# fmc_connector.net
KiCad netlist of a schematic drawn in Altium Designer
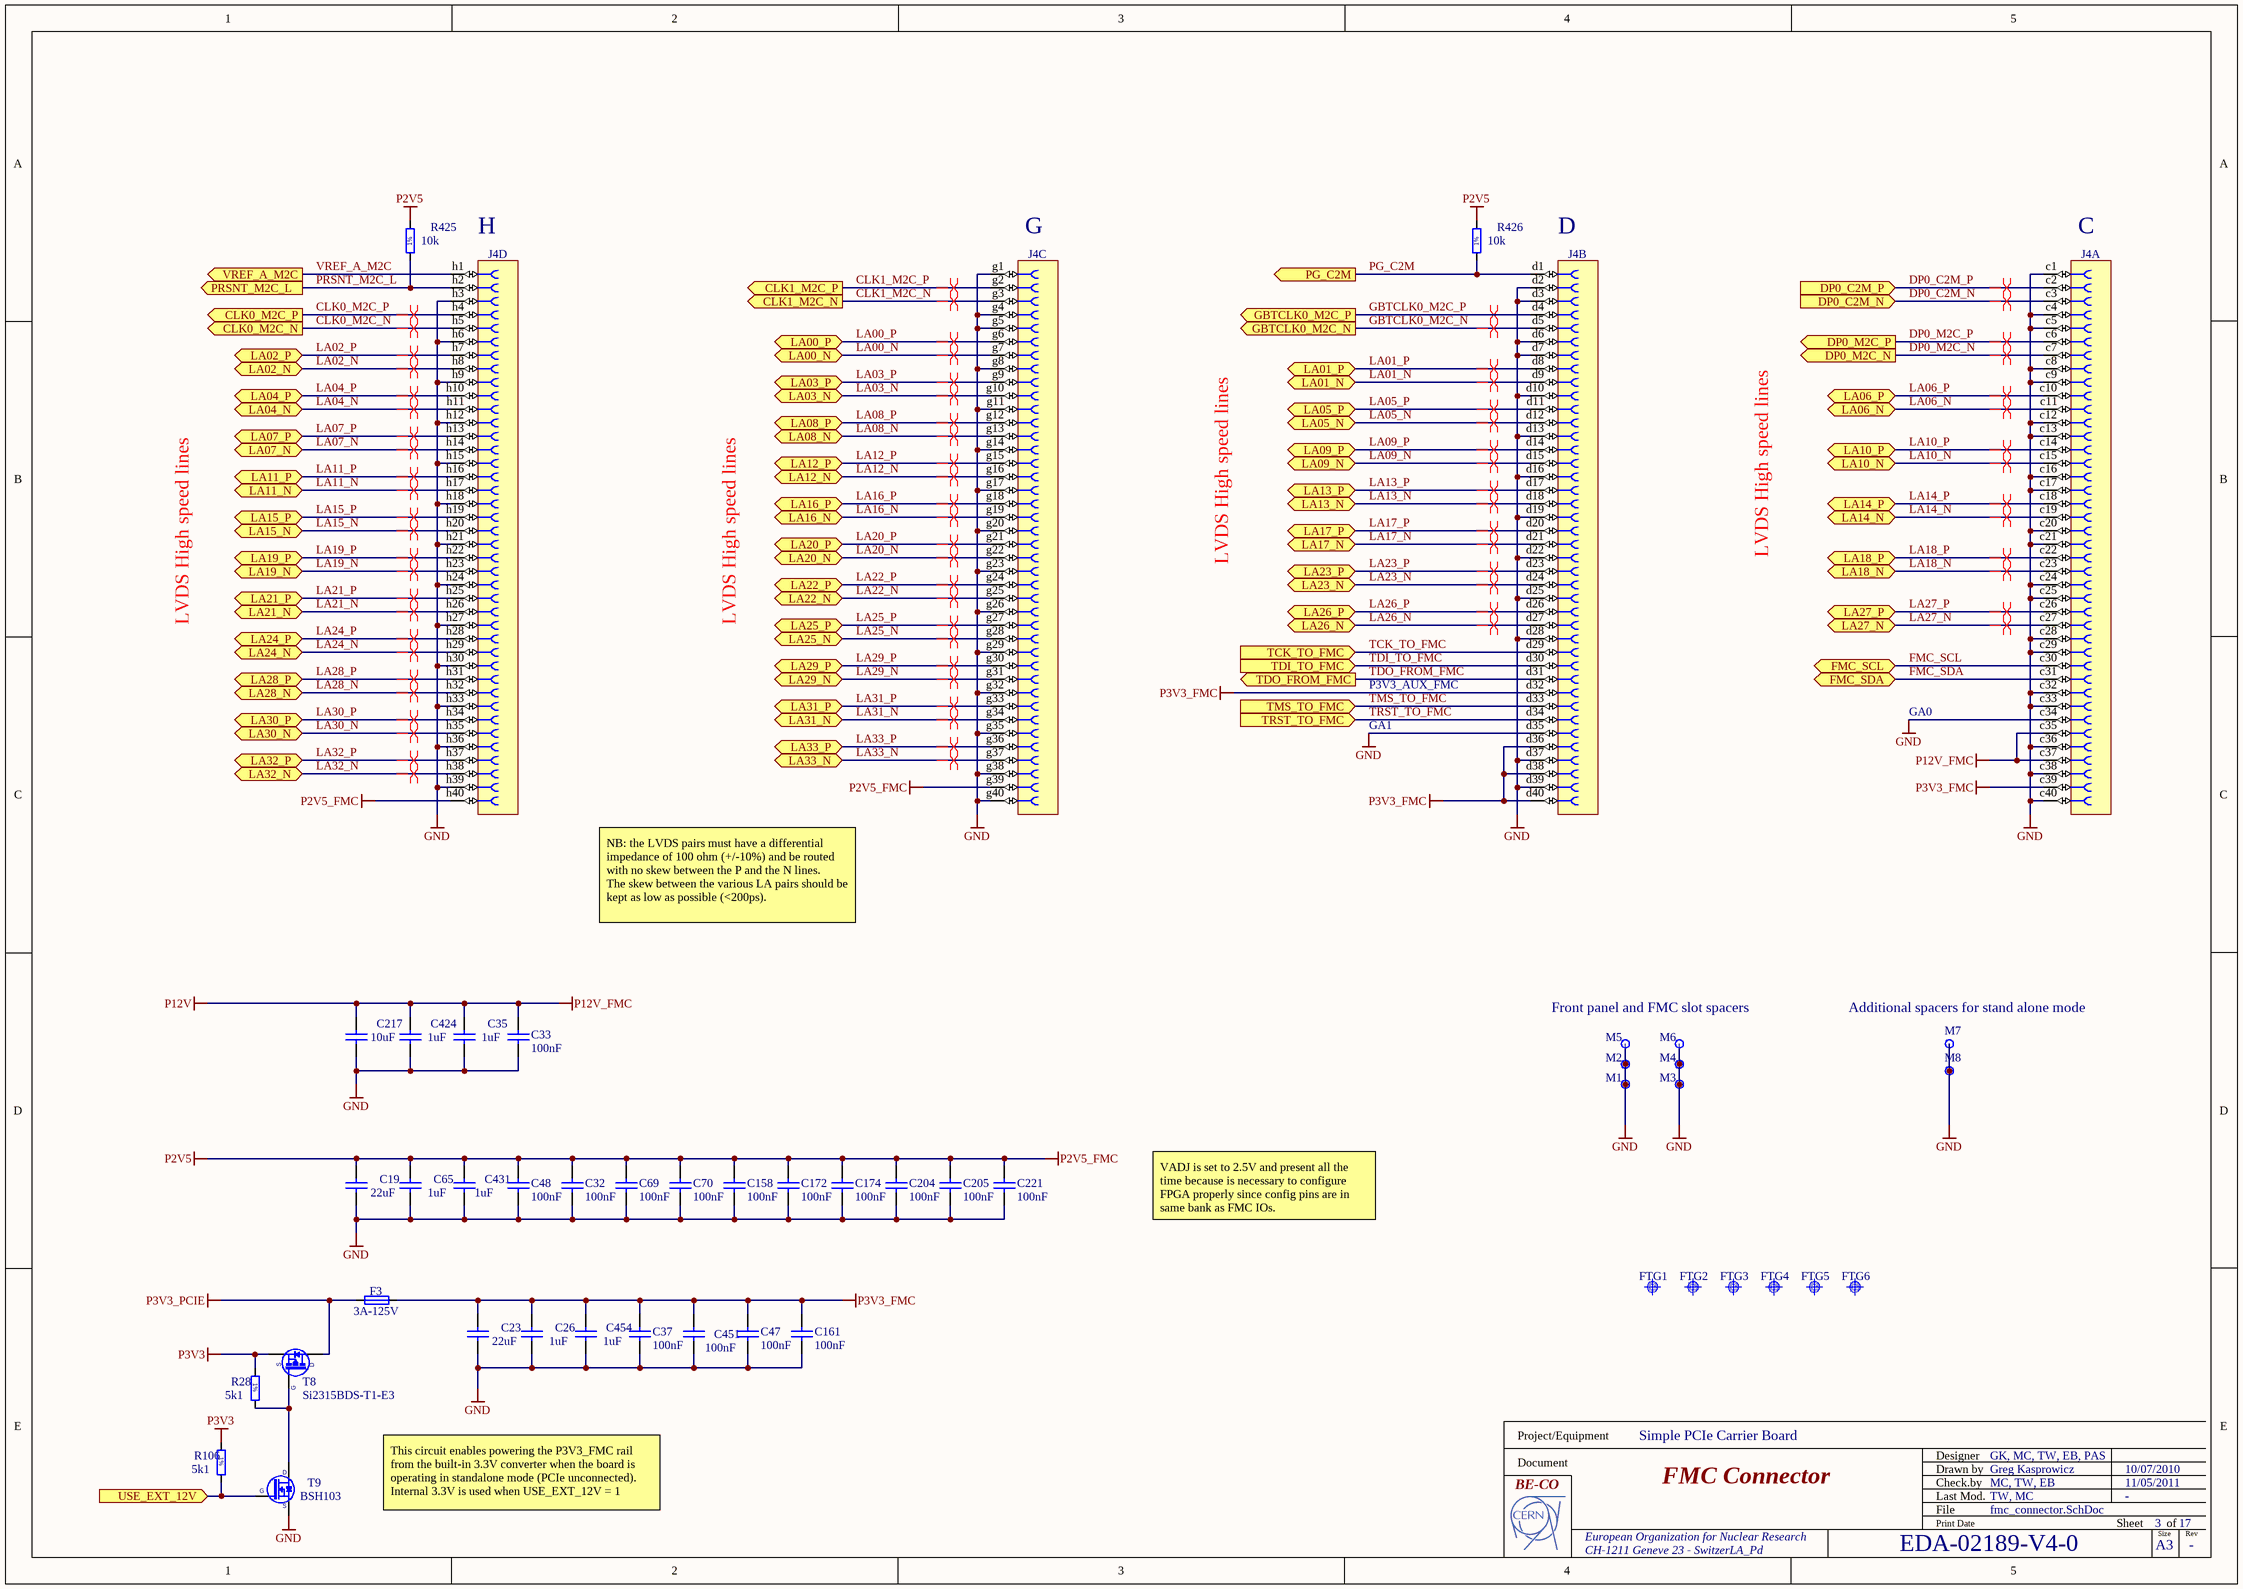
[diagram p0: fmc_connector.SchDoc]

(export (version "E")
  (design (tool "Eeschema 10.0.6"))
  (components
    (comp (ref "C19")
      (value "22uF")
      (footprint "CAPC3216X180N")
      (description "Non-polarised capacitor")
      (fields
        (field (name "PART NUMBER") "CC1206_22UF_10V_10%_X7R")
        (field (name "VOLTAGE") "10V")
        (field (name "AUTHOR") "CERN DEM JLC")
      )
      (libsource (lib "Capacitors") (part "Capacitor - non polarized"))
    )
    (comp (ref "C23")
      (value "22uF")
      (footprint "CAPC3216X180N")
      (description "Non-polarised capacitor")
      (fields
        (field (name "PART NUMBER") "CC1206_22UF_10V_10%_X7R")
        (field (name "VOLTAGE") "10V")
        (field (name "AUTHOR") "CERN DEM JLC")
      )
      (libsource (lib "Capacitors") (part "Capacitor - non polarized"))
    )
    (comp (ref "C26")
      (value "1uF")
      (footprint "CAPC1608X87N")
      (description "Non-polarised capacitor")
      (fields
        (field (name "PART NUMBER") "CC0603_1UF_16V_10%_X7R")
        (field (name "VOLTAGE") "16V")
        (field (name "AUTHOR") "CERN DEM JLC")
      )
      (libsource (lib "Capacitors") (part "Capacitor - non polarized"))
    )
    (comp (ref "C32")
      (value "100nF")
      (footprint "CAPC1608X87N")
      (description "Non-polarised capacitor")
      (fields
        (field (name "PART NUMBER") "CC0603_100NF_50V_10%_X7R")
        (field (name "VOLTAGE") "50V")
        (field (name "AUTHOR") "CERN DEM JLC")
      )
      (libsource (lib "Capacitors") (part "Capacitor - non polarized"))
    )
    (comp (ref "C33")
      (value "100nF")
      (footprint "CAPC1608X87N")
      (description "Non-polarised capacitor")
      (fields
        (field (name "PART NUMBER") "CC0603_100NF_50V_10%_X7R")
        (field (name "VOLTAGE") "50V")
        (field (name "AUTHOR") "CERN DEM JLC")
      )
      (libsource (lib "Capacitors") (part "Capacitor - non polarized"))
    )
    (comp (ref "C35")
      (value "1uF")
      (footprint "CAPC1608X87N")
      (description "Non-polarised capacitor")
      (fields
        (field (name "PART NUMBER") "CC0603_1UF_16V_10%_X7R")
        (field (name "VOLTAGE") "16V")
        (field (name "AUTHOR") "CERN DEM JLC")
      )
      (libsource (lib "Capacitors") (part "Capacitor - non polarized"))
    )
    (comp (ref "C37")
      (value "100nF")
      (footprint "CAPC1608X87N")
      (description "Non-polarised capacitor")
      (fields
        (field (name "PART NUMBER") "CC0603_100NF_50V_10%_X7R")
        (field (name "VOLTAGE") "50V")
        (field (name "AUTHOR") "CERN DEM JLC")
      )
      (libsource (lib "Capacitors") (part "Capacitor - non polarized"))
    )
    (comp (ref "C47")
      (value "100nF")
      (footprint "CAPC1608X87N")
      (description "Non-polarised capacitor")
      (fields
        (field (name "PART NUMBER") "CC0603_100NF_50V_10%_X7R")
        (field (name "VOLTAGE") "50V")
        (field (name "AUTHOR") "CERN DEM JLC")
      )
      (libsource (lib "Capacitors") (part "Capacitor - non polarized"))
    )
    (comp (ref "C48")
      (value "100nF")
      (footprint "CAPC1608X87N")
      (description "Non-polarised capacitor")
      (fields
        (field (name "PART NUMBER") "CC0603_100NF_50V_10%_X7R")
        (field (name "VOLTAGE") "50V")
        (field (name "AUTHOR") "CERN DEM JLC")
      )
      (libsource (lib "Capacitors") (part "Capacitor - non polarized"))
    )
    (comp (ref "C65")
      (value "1uF")
      (footprint "CAPC1608X87N")
      (description "Non-polarised capacitor")
      (fields
        (field (name "PART NUMBER") "CC0603_1UF_16V_10%_X7R")
        (field (name "VOLTAGE") "16V")
        (field (name "AUTHOR") "CERN DEM JLC")
      )
      (libsource (lib "Capacitors") (part "Capacitor - non polarized"))
    )
    (comp (ref "C69")
      (value "100nF")
      (footprint "CAPC1608X87N")
      (description "Non-polarised capacitor")
      (fields
        (field (name "PART NUMBER") "CC0603_100NF_50V_10%_X7R")
        (field (name "VOLTAGE") "50V")
        (field (name "AUTHOR") "CERN DEM JLC")
      )
      (libsource (lib "Capacitors") (part "Capacitor - non polarized"))
    )
    (comp (ref "C70")
      (value "100nF")
      (footprint "CAPC1608X87N")
      (description "Non-polarised capacitor")
      (fields
        (field (name "PART NUMBER") "CC0603_100NF_50V_10%_X7R")
        (field (name "VOLTAGE") "50V")
        (field (name "AUTHOR") "CERN DEM JLC")
      )
      (libsource (lib "Capacitors") (part "Capacitor - non polarized"))
    )
    (comp (ref "C158")
      (value "100nF")
      (footprint "CAPC1608X87N")
      (description "Non-polarised capacitor")
      (fields
        (field (name "PART NUMBER") "CC0603_100NF_50V_10%_X7R")
        (field (name "VOLTAGE") "50V")
        (field (name "AUTHOR") "CERN DEM JLC")
      )
      (libsource (lib "Capacitors") (part "Capacitor - non polarized"))
    )
    (comp (ref "C161")
      (value "100nF")
      (footprint "CAPC1608X87N")
      (description "Non-polarised capacitor")
      (fields
        (field (name "PART NUMBER") "CC0603_100NF_50V_10%_X7R")
        (field (name "VOLTAGE") "50V")
        (field (name "AUTHOR") "CERN DEM JLC")
      )
      (libsource (lib "Capacitors") (part "Capacitor - non polarized"))
    )
    (comp (ref "C172")
      (value "100nF")
      (footprint "CAPC1608X87N")
      (description "Non-polarised capacitor")
      (fields
        (field (name "PART NUMBER") "CC0603_100NF_50V_10%_X7R")
        (field (name "VOLTAGE") "50V")
        (field (name "AUTHOR") "CERN DEM JLC")
      )
      (libsource (lib "Capacitors") (part "Capacitor - non polarized"))
    )
    (comp (ref "C174")
      (value "100nF")
      (footprint "CAPC1608X87N")
      (description "Non-polarised capacitor")
      (fields
        (field (name "PART NUMBER") "CC0603_100NF_50V_10%_X7R")
        (field (name "VOLTAGE") "50V")
        (field (name "AUTHOR") "CERN DEM JLC")
      )
      (libsource (lib "Capacitors") (part "Capacitor - non polarized"))
    )
    (comp (ref "C204")
      (value "100nF")
      (footprint "CAPC1608X87N")
      (description "Non-polarised capacitor")
      (fields
        (field (name "PART NUMBER") "CC0603_100NF_50V_10%_X7R")
        (field (name "VOLTAGE") "50V")
        (field (name "AUTHOR") "CERN DEM JLC")
      )
      (libsource (lib "Capacitors") (part "Capacitor - non polarized"))
    )
    (comp (ref "C205")
      (value "100nF")
      (footprint "CAPC1608X87N")
      (description "Non-polarised capacitor")
      (fields
        (field (name "PART NUMBER") "CC0603_100NF_50V_10%_X7R")
        (field (name "VOLTAGE") "50V")
        (field (name "AUTHOR") "CERN DEM JLC")
      )
      (libsource (lib "Capacitors") (part "Capacitor - non polarized"))
    )
    (comp (ref "C217")
      (value "10uF")
      (footprint "CAPC3225X270N")
      (description "Non-polarised capacitor")
      (fields
        (field (name "PART NUMBER") "CC1210_10UF_25V_10%_X7R")
        (field (name "VOLTAGE") "25V")
        (field (name "AUTHOR") "CERN DEM JLC")
      )
      (libsource (lib "Capacitors") (part "Capacitor - non polarized"))
    )
    (comp (ref "C221")
      (value "100nF")
      (footprint "CAPC1608X87N")
      (description "Non-polarised capacitor")
      (fields
        (field (name "PART NUMBER") "CC0603_100NF_50V_10%_X7R")
        (field (name "VOLTAGE") "50V")
        (field (name "AUTHOR") "CERN DEM JLC")
      )
      (libsource (lib "Capacitors") (part "Capacitor - non polarized"))
    )
    (comp (ref "C424")
      (value "1uF")
      (footprint "CAPC1608X87N")
      (description "Non-polarised capacitor")
      (fields
        (field (name "PART NUMBER") "CC0603_1UF_16V_10%_X7R")
        (field (name "VOLTAGE") "16V")
        (field (name "AUTHOR") "CERN DEM JLC")
      )
      (libsource (lib "Capacitors") (part "Capacitor - non polarized"))
    )
    (comp (ref "C431")
      (value "1uF")
      (footprint "CAPC1608X87N")
      (description "Non-polarised capacitor")
      (fields
        (field (name "PART NUMBER") "CC0603_1UF_16V_10%_X7R")
        (field (name "VOLTAGE") "16V")
        (field (name "AUTHOR") "CERN DEM JLC")
      )
      (libsource (lib "Capacitors") (part "Capacitor - non polarized"))
    )
    (comp (ref "C451")
      (value "100nF")
      (footprint "CAPC1608X87N")
      (description "Non-polarised capacitor")
      (fields
        (field (name "PART NUMBER") "CC0603_100NF_50V_10%_X7R")
        (field (name "VOLTAGE") "50V")
        (field (name "AUTHOR") "CERN DEM JLC")
      )
      (libsource (lib "Capacitors") (part "Capacitor - non polarized"))
    )
    (comp (ref "C454")
      (value "1uF")
      (footprint "CAPC1608X87N")
      (description "Non-polarised capacitor")
      (fields
        (field (name "PART NUMBER") "CC0603_1UF_16V_10%_X7R")
        (field (name "VOLTAGE") "16V")
        (field (name "AUTHOR") "CERN DEM JLC")
      )
      (libsource (lib "Capacitors") (part "Capacitor - non polarized"))
    )
    (comp (ref "F3")
      (value "3A-125V")
      (footprint "FUSE_LITTELFUSE_0154")
      (description "Fuse")
      (fields
        (field (name "PART NUMBER") "FUSE_LITTELFUSE_0154003.DR")
        (field (name "MANUFACTURER") "LITTELFUSE")
        (field (name "AUTHOR") "CERN DEM JMW")
      )
      (libsource (lib "Eletro-mechanical") (part "Fuse"))
    )
    (comp (ref "FTG1")
      (value "Use only in PCB")
      (footprint "FIDUCIAL_TOP_S100-200")
      (description "Fiducial Target")
      (fields (field (name "PART NUMBER") "FIDUCIAL_TARGET_S100-200") (field (name "AUTHOR") "CERN DEM JLC"))
      (libsource (lib "Eletro-mechanical") (part "Fiducial Target"))
    )
    (comp (ref "FTG2")
      (value "Use only in PCB")
      (footprint "FIDUCIAL_TOP_S100-200")
      (description "Fiducial Target")
      (fields (field (name "PART NUMBER") "FIDUCIAL_TARGET_S100-200") (field (name "AUTHOR") "CERN DEM JLC"))
      (libsource (lib "Eletro-mechanical") (part "Fiducial Target"))
    )
    (comp (ref "FTG3")
      (value "Use only in PCB")
      (footprint "FIDUCIAL_TOP_S100-200")
      (description "Fiducial Target")
      (fields (field (name "PART NUMBER") "FIDUCIAL_TARGET_S100-200") (field (name "AUTHOR") "CERN DEM JLC"))
      (libsource (lib "Eletro-mechanical") (part "Fiducial Target"))
    )
    (comp (ref "FTG4")
      (value "Use only in PCB")
      (footprint "FIDUCIAL_TOP_S100-200")
      (description "Fiducial Target")
      (fields (field (name "PART NUMBER") "FIDUCIAL_TARGET_S100-200") (field (name "AUTHOR") "CERN DEM JLC"))
      (libsource (lib "Eletro-mechanical") (part "Fiducial Target"))
    )
    (comp (ref "FTG5")
      (value "Use only in PCB")
      (footprint "FIDUCIAL_TOP_S100-200")
      (description "Fiducial Target")
      (fields (field (name "PART NUMBER") "FIDUCIAL_TARGET_S100-200") (field (name "AUTHOR") "CERN DEM JLC"))
      (libsource (lib "Eletro-mechanical") (part "Fiducial Target"))
    )
    (comp (ref "FTG6")
      (value "Use only in PCB")
      (footprint "FIDUCIAL_TOP_S100-200")
      (description "Fiducial Target")
      (fields (field (name "PART NUMBER") "FIDUCIAL_TARGET_S100-200") (field (name "AUTHOR") "CERN DEM JLC"))
      (libsource (lib "Eletro-mechanical") (part "Fiducial Target"))
    )
    (comp (ref "J4")
      (value "VITA 57")
      (footprint "SAMTEC_ASP-134603-01")
      (description "Connector VITA 57, 160 Female contacts in 4 row cdgh")
      (fields
        (field (name "PART NUMBER") "SAMTEC_ASP-134603-01")
        (field (name "MANUFACTURER") "SAMTEC")
        (field (name "AUTHOR") "CERN DEM JLC")
      )
      (libsource (lib "Connectors") (part "Connector VITA 57 160 Female (cdgh)"))
    )
    (comp (ref "M1")
      (value "Plated Hole")
      (footprint "MTG300_600")
      (description "Single Terminal Socket")
      (fields (field (name "PART NUMBER") "PLATED_HOLE3.0_PAD6.0") (field (name "AUTHOR") "CERN DEM JLC"))
      (libsource (lib "Eletro-mechanical") (part "Single Terminal Socket"))
    )
    (comp (ref "M2")
      (value "Plated Hole")
      (footprint "MTG300_600")
      (description "Single Terminal Socket")
      (fields (field (name "PART NUMBER") "PLATED_HOLE3.0_PAD6.0") (field (name "AUTHOR") "CERN DEM JLC"))
      (libsource (lib "Eletro-mechanical") (part "Single Terminal Socket"))
    )
    (comp (ref "M3")
      (value "Plated Hole")
      (footprint "MTG300_600")
      (description "Single Terminal Socket")
      (fields (field (name "PART NUMBER") "PLATED_HOLE3.0_PAD6.0") (field (name "AUTHOR") "CERN DEM JLC"))
      (libsource (lib "Eletro-mechanical") (part "Single Terminal Socket"))
    )
    (comp (ref "M4")
      (value "Plated Hole")
      (footprint "MTG300_600")
      (description "Single Terminal Socket")
      (fields (field (name "PART NUMBER") "PLATED_HOLE3.0_PAD6.0") (field (name "AUTHOR") "CERN DEM JLC"))
      (libsource (lib "Eletro-mechanical") (part "Single Terminal Socket"))
    )
    (comp (ref "M5")
      (value "Plated Hole")
      (footprint "MTG300_600")
      (description "Single Terminal Socket")
      (fields (field (name "PART NUMBER") "PLATED_HOLE3.0_PAD6.0") (field (name "AUTHOR") "CERN DEM JLC"))
      (libsource (lib "Eletro-mechanical") (part "Single Terminal Socket"))
    )
    (comp (ref "M6")
      (value "Plated Hole")
      (footprint "MTG300_600")
      (description "Single Terminal Socket")
      (fields (field (name "PART NUMBER") "PLATED_HOLE3.0_PAD6.0") (field (name "AUTHOR") "CERN DEM JLC"))
      (libsource (lib "Eletro-mechanical") (part "Single Terminal Socket"))
    )
    (comp (ref "M7")
      (value "Plated Hole")
      (footprint "MTG300_600")
      (description "Single Terminal Socket")
      (fields (field (name "PART NUMBER") "PLATED_HOLE3.0_PAD6.0") (field (name "AUTHOR") "CERN DEM JLC"))
      (libsource (lib "Eletro-mechanical") (part "Single Terminal Socket"))
    )
    (comp (ref "M8")
      (value "Plated Hole")
      (footprint "MTG300_600")
      (description "Single Terminal Socket")
      (fields (field (name "PART NUMBER") "PLATED_HOLE3.0_PAD6.0") (field (name "AUTHOR") "CERN DEM JLC"))
      (libsource (lib "Eletro-mechanical") (part "Single Terminal Socket"))
    )
    (comp (ref "R28")
      (value "5k1")
      (footprint "RESC1608X55N")
      (description "Resistor - 1%")
      (fields
        (field (name "PART NUMBER") "R0603_5K1_1%_0.1W_100PPM")
        (field (name "POWER") "0.1W")
        (field (name "AUTHOR") "CERN DEM JLC")
      )
      (libsource (lib "Resistors") (part "Resistor - 1%"))
    )
    (comp (ref "R106")
      (value "5k1")
      (footprint "RESC1608X55N")
      (description "Resistor - 1%")
      (fields
        (field (name "PART NUMBER") "R0603_5K1_1%_0.1W_100PPM")
        (field (name "POWER") "0.1W")
        (field (name "AUTHOR") "CERN DEM JLC")
      )
      (libsource (lib "Resistors") (part "Resistor - 1%"))
    )
    (comp (ref "R425")
      (value "10k")
      (footprint "RESC1608X55N")
      (description "Resistor - 1%")
      (fields
        (field (name "PART NUMBER") "R0603_10K_1%_0.1W_100PPM")
        (field (name "POWER") "0.1W")
        (field (name "AUTHOR") "CERN DEM JLC")
      )
      (libsource (lib "Resistors") (part "Resistor - 1%"))
    )
    (comp (ref "R426")
      (value "10k")
      (footprint "RESC1608X55N")
      (description "Resistor - 1%")
      (fields
        (field (name "PART NUMBER") "R0603_10K_1%_0.1W_100PPM")
        (field (name "POWER") "0.1W")
        (field (name "AUTHOR") "CERN DEM JLC")
      )
      (libsource (lib "Resistors") (part "Resistor - 1%"))
    )
    (comp (ref "T8")
      (value "Si2315BDS-T1-E3")
      (footprint "SOT95P237X112-3N")
      (description "P-CHANNEL MOSFET WITH DIODE")
      (fields (field (name "MANUFACTURER") "VISHAY SILICONIX") (field (name "AUTHOR") "CERN DEM JLC"))
      (libsource (lib "ICs And Semiconductors") (part "P-MOSFET-D 1G 2S 3D"))
    )
    (comp (ref "T9")
      (value "BSH103")
      (footprint "SOT95P230X110-3N")
      (description "N-CHANNEL MOSFET WITH DIODE")
      (fields (field (name "MANUFACTURER") "NXP SEMICONDUCTORS") (field (name "AUTHOR") "CERN DEM JLC"))
      (libsource (lib "ICs And Semiconductors") (part "N-MOSFET-D 1G 2S 3D"))
    )
  )
  (nets
    (net (code "1") (name "/CLK0_M2C_N") (class "Default")
      (node (ref "J4") (pin "h5") (pinfunction "h5_h5") (pintype "bidirectional"))
    )
    (net (code "2") (name "/CLK0_M2C_P") (class "Default")
      (node (ref "J4") (pin "h4") (pinfunction "h4_h4") (pintype "bidirectional"))
    )
    (net (code "3") (name "/CLK1_M2C_N") (class "Default")
      (node (ref "J4") (pin "g3") (pinfunction "g3_g3") (pintype "bidirectional"))
    )
    (net (code "4") (name "/CLK1_M2C_P") (class "Default")
      (node (ref "J4") (pin "g2") (pinfunction "g2_g2") (pintype "bidirectional"))
    )
    (net (code "5") (name "/DP0_C2M_N") (class "Default")
      (node (ref "J4") (pin "c3") (pinfunction "c3_c3") (pintype "bidirectional"))
    )
    (net (code "6") (name "/DP0_C2M_P") (class "Default")
      (node (ref "J4") (pin "c2") (pinfunction "c2_c2") (pintype "bidirectional"))
    )
    (net (code "7") (name "/DP0_M2C_N") (class "Default")
      (node (ref "J4") (pin "c7") (pinfunction "c7_c7") (pintype "bidirectional"))
    )
    (net (code "8") (name "/DP0_M2C_P") (class "Default")
      (node (ref "J4") (pin "c6") (pinfunction "c6_c6") (pintype "bidirectional"))
    )
    (net (code "9") (name "/FMC_SCL") (class "Default")
      (node (ref "J4") (pin "c30") (pinfunction "c30_c30") (pintype "bidirectional"))
    )
    (net (code "10") (name "/FMC_SDA") (class "Default")
      (node (ref "J4") (pin "c31") (pinfunction "c31_c31") (pintype "bidirectional"))
    )
    (net (code "11") (name "/GBTCLK0_M2C_N") (class "Default")
      (node (ref "J4") (pin "d5") (pinfunction "d5_d5") (pintype "bidirectional"))
    )
    (net (code "12") (name "/GBTCLK0_M2C_P") (class "Default")
      (node (ref "J4") (pin "d4") (pinfunction "d4_d4") (pintype "bidirectional"))
    )
    (net (code "13") (name "/LA00_N") (class "Default")
      (node (ref "J4") (pin "g7") (pinfunction "g7_g7") (pintype "bidirectional"))
    )
    (net (code "14") (name "/LA00_P") (class "Default")
      (node (ref "J4") (pin "g6") (pinfunction "g6_g6") (pintype "bidirectional"))
    )
    (net (code "15") (name "/LA01_N") (class "Default")
      (node (ref "J4") (pin "d9") (pinfunction "d9_d9") (pintype "bidirectional"))
    )
    (net (code "16") (name "/LA01_P") (class "Default")
      (node (ref "J4") (pin "d8") (pinfunction "d8_d8") (pintype "bidirectional"))
    )
    (net (code "17") (name "/LA02_N") (class "Default")
      (node (ref "J4") (pin "h8") (pinfunction "h8_h8") (pintype "bidirectional"))
    )
    (net (code "18") (name "/LA02_P") (class "Default")
      (node (ref "J4") (pin "h7") (pinfunction "h7_h7") (pintype "bidirectional"))
    )
    (net (code "19") (name "/LA03_N") (class "Default")
      (node (ref "J4") (pin "g10") (pinfunction "g10_g10") (pintype "bidirectional"))
    )
    (net (code "20") (name "/LA03_P") (class "Default")
      (node (ref "J4") (pin "g9") (pinfunction "g9_g9") (pintype "bidirectional"))
    )
    (net (code "21") (name "/LA04_N") (class "Default")
      (node (ref "J4") (pin "h11") (pinfunction "h11_h11") (pintype "bidirectional"))
    )
    (net (code "22") (name "/LA04_P") (class "Default")
      (node (ref "J4") (pin "h10") (pinfunction "h10_h10") (pintype "bidirectional"))
    )
    (net (code "23") (name "/LA05_N") (class "Default")
      (node (ref "J4") (pin "d12") (pinfunction "d12_d12") (pintype "bidirectional"))
    )
    (net (code "24") (name "/LA05_P") (class "Default")
      (node (ref "J4") (pin "d11") (pinfunction "d11_d11") (pintype "bidirectional"))
    )
    (net (code "25") (name "/LA06_N") (class "Default")
      (node (ref "J4") (pin "c11") (pinfunction "c11_c11") (pintype "bidirectional"))
    )
    (net (code "26") (name "/LA06_P") (class "Default")
      (node (ref "J4") (pin "c10") (pinfunction "c10_c10") (pintype "bidirectional"))
    )
    (net (code "27") (name "/LA07_N") (class "Default")
      (node (ref "J4") (pin "h14") (pinfunction "h14_h14") (pintype "bidirectional"))
    )
    (net (code "28") (name "/LA07_P") (class "Default")
      (node (ref "J4") (pin "h13") (pinfunction "h13_h13") (pintype "bidirectional"))
    )
    (net (code "29") (name "/LA08_N") (class "Default")
      (node (ref "J4") (pin "g13") (pinfunction "g13_g13") (pintype "bidirectional"))
    )
    (net (code "30") (name "/LA08_P") (class "Default")
      (node (ref "J4") (pin "g12") (pinfunction "g12_g12") (pintype "bidirectional"))
    )
    (net (code "31") (name "/LA09_N") (class "Default")
      (node (ref "J4") (pin "d15") (pinfunction "d15_d15") (pintype "bidirectional"))
    )
    (net (code "32") (name "/LA09_P") (class "Default")
      (node (ref "J4") (pin "d14") (pinfunction "d14_d14") (pintype "bidirectional"))
    )
    (net (code "33") (name "/LA10_N") (class "Default")
      (node (ref "J4") (pin "c15") (pinfunction "c15_c15") (pintype "bidirectional"))
    )
    (net (code "34") (name "/LA10_P") (class "Default")
      (node (ref "J4") (pin "c14") (pinfunction "c14_c14") (pintype "bidirectional"))
    )
    (net (code "35") (name "/LA11_N") (class "Default")
      (node (ref "J4") (pin "h17") (pinfunction "h17_h17") (pintype "bidirectional"))
    )
    (net (code "36") (name "/LA11_P") (class "Default")
      (node (ref "J4") (pin "h16") (pinfunction "h16_h16") (pintype "bidirectional"))
    )
    (net (code "37") (name "/LA12_N") (class "Default")
      (node (ref "J4") (pin "g16") (pinfunction "g16_g16") (pintype "bidirectional"))
    )
    (net (code "38") (name "/LA12_P") (class "Default")
      (node (ref "J4") (pin "g15") (pinfunction "g15_g15") (pintype "bidirectional"))
    )
    (net (code "39") (name "/LA13_N") (class "Default")
      (node (ref "J4") (pin "d18") (pinfunction "d18_d18") (pintype "bidirectional"))
    )
    (net (code "40") (name "/LA13_P") (class "Default")
      (node (ref "J4") (pin "d17") (pinfunction "d17_d17") (pintype "bidirectional"))
    )
    (net (code "41") (name "/LA14_N") (class "Default")
      (node (ref "J4") (pin "c19") (pinfunction "c19_c19") (pintype "bidirectional"))
    )
    (net (code "42") (name "/LA14_P") (class "Default")
      (node (ref "J4") (pin "c18") (pinfunction "c18_c18") (pintype "bidirectional"))
    )
    (net (code "43") (name "/LA15_N") (class "Default")
      (node (ref "J4") (pin "h20") (pinfunction "h20_h20") (pintype "bidirectional"))
    )
    (net (code "44") (name "/LA15_P") (class "Default")
      (node (ref "J4") (pin "h19") (pinfunction "h19_h19") (pintype "bidirectional"))
    )
    (net (code "45") (name "/LA16_N") (class "Default")
      (node (ref "J4") (pin "g19") (pinfunction "g19_g19") (pintype "bidirectional"))
    )
    (net (code "46") (name "/LA16_P") (class "Default")
      (node (ref "J4") (pin "g18") (pinfunction "g18_g18") (pintype "bidirectional"))
    )
    (net (code "47") (name "/LA17_N") (class "Default")
      (node (ref "J4") (pin "d21") (pinfunction "d21_d21") (pintype "bidirectional"))
    )
    (net (code "48") (name "/LA17_P") (class "Default")
      (node (ref "J4") (pin "d20") (pinfunction "d20_d20") (pintype "bidirectional"))
    )
    (net (code "49") (name "/LA18_N") (class "Default")
      (node (ref "J4") (pin "c23") (pinfunction "c23_c23") (pintype "bidirectional"))
    )
    (net (code "50") (name "/LA18_P") (class "Default")
      (node (ref "J4") (pin "c22") (pinfunction "c22_c22") (pintype "bidirectional"))
    )
    (net (code "51") (name "/LA19_N") (class "Default")
      (node (ref "J4") (pin "h23") (pinfunction "h23_h23") (pintype "bidirectional"))
    )
    (net (code "52") (name "/LA19_P") (class "Default")
      (node (ref "J4") (pin "h22") (pinfunction "h22_h22") (pintype "bidirectional"))
    )
    (net (code "53") (name "/LA20_N") (class "Default")
      (node (ref "J4") (pin "g22") (pinfunction "g22_g22") (pintype "bidirectional"))
    )
    (net (code "54") (name "/LA20_P") (class "Default")
      (node (ref "J4") (pin "g21") (pinfunction "g21_g21") (pintype "bidirectional"))
    )
    (net (code "55") (name "/LA21_N") (class "Default")
      (node (ref "J4") (pin "h26") (pinfunction "h26_h26") (pintype "bidirectional"))
    )
    (net (code "56") (name "/LA21_P") (class "Default")
      (node (ref "J4") (pin "h25") (pinfunction "h25_h25") (pintype "bidirectional"))
    )
    (net (code "57") (name "/LA22_N") (class "Default")
      (node (ref "J4") (pin "g25") (pinfunction "g25_g25") (pintype "bidirectional"))
    )
    (net (code "58") (name "/LA22_P") (class "Default")
      (node (ref "J4") (pin "g24") (pinfunction "g24_g24") (pintype "bidirectional"))
    )
    (net (code "59") (name "/LA23_N") (class "Default")
      (node (ref "J4") (pin "d24") (pinfunction "d24_d24") (pintype "bidirectional"))
    )
    (net (code "60") (name "/LA23_P") (class "Default")
      (node (ref "J4") (pin "d23") (pinfunction "d23_d23") (pintype "bidirectional"))
    )
    (net (code "61") (name "/LA24_N") (class "Default")
      (node (ref "J4") (pin "h29") (pinfunction "h29_h29") (pintype "bidirectional"))
    )
    (net (code "62") (name "/LA24_P") (class "Default")
      (node (ref "J4") (pin "h28") (pinfunction "h28_h28") (pintype "bidirectional"))
    )
    (net (code "63") (name "/LA25_N") (class "Default")
      (node (ref "J4") (pin "g28") (pinfunction "g28_g28") (pintype "bidirectional"))
    )
    (net (code "64") (name "/LA25_P") (class "Default")
      (node (ref "J4") (pin "g27") (pinfunction "g27_g27") (pintype "bidirectional"))
    )
    (net (code "65") (name "/LA26_N") (class "Default")
      (node (ref "J4") (pin "d27") (pinfunction "d27_d27") (pintype "bidirectional"))
    )
    (net (code "66") (name "/LA26_P") (class "Default")
      (node (ref "J4") (pin "d26") (pinfunction "d26_d26") (pintype "bidirectional"))
    )
    (net (code "67") (name "/LA27_N") (class "Default")
      (node (ref "J4") (pin "c27") (pinfunction "c27_c27") (pintype "bidirectional"))
    )
    (net (code "68") (name "/LA27_P") (class "Default")
      (node (ref "J4") (pin "c26") (pinfunction "c26_c26") (pintype "bidirectional"))
    )
    (net (code "69") (name "/LA28_N") (class "Default")
      (node (ref "J4") (pin "h32") (pinfunction "h32_h32") (pintype "bidirectional"))
    )
    (net (code "70") (name "/LA28_P") (class "Default")
      (node (ref "J4") (pin "h31") (pinfunction "h31_h31") (pintype "bidirectional"))
    )
    (net (code "71") (name "/LA29_N") (class "Default")
      (node (ref "J4") (pin "g31") (pinfunction "g31_g31") (pintype "bidirectional"))
    )
    (net (code "72") (name "/LA29_P") (class "Default")
      (node (ref "J4") (pin "g30") (pinfunction "g30_g30") (pintype "bidirectional"))
    )
    (net (code "73") (name "/LA30_N") (class "Default")
      (node (ref "J4") (pin "h35") (pinfunction "h35_h35") (pintype "bidirectional"))
    )
    (net (code "74") (name "/LA30_P") (class "Default")
      (node (ref "J4") (pin "h34") (pinfunction "h34_h34") (pintype "bidirectional"))
    )
    (net (code "75") (name "/LA31_N") (class "Default")
      (node (ref "J4") (pin "g34") (pinfunction "g34_g34") (pintype "bidirectional"))
    )
    (net (code "76") (name "/LA31_P") (class "Default")
      (node (ref "J4") (pin "g33") (pinfunction "g33_g33") (pintype "bidirectional"))
    )
    (net (code "77") (name "/LA32_N") (class "Default")
      (node (ref "J4") (pin "h38") (pinfunction "h38_h38") (pintype "bidirectional"))
    )
    (net (code "78") (name "/LA32_P") (class "Default")
      (node (ref "J4") (pin "h37") (pinfunction "h37_h37") (pintype "bidirectional"))
    )
    (net (code "79") (name "/LA33_N") (class "Default")
      (node (ref "J4") (pin "g37") (pinfunction "g37_g37") (pintype "bidirectional"))
    )
    (net (code "80") (name "/LA33_P") (class "Default")
      (node (ref "J4") (pin "g36") (pinfunction "g36_g36") (pintype "bidirectional"))
    )
    (net (code "81") (name "/PG_C2M") (class "Default")
      (node (ref "J4") (pin "d1") (pinfunction "d1_d1") (pintype "bidirectional"))
      (node (ref "R426") (pin "1") (pinfunction "1_1") (pintype "passive"))
    )
    (net (code "82") (name "/PRSNT_M2C_L") (class "Default")
      (node (ref "J4") (pin "h2") (pinfunction "h2_h2") (pintype "bidirectional"))
      (node (ref "R425") (pin "1") (pinfunction "1_1") (pintype "passive"))
    )
    (net (code "83") (name "/TCK_TO_FMC") (class "Default")
      (node (ref "J4") (pin "d29") (pinfunction "d29_d29") (pintype "bidirectional"))
    )
    (net (code "84") (name "/TDI_TO_FMC") (class "Default")
      (node (ref "J4") (pin "d30") (pinfunction "d30_d30") (pintype "bidirectional"))
    )
    (net (code "85") (name "/TDO_FROM_FMC") (class "Default")
      (node (ref "J4") (pin "d31") (pinfunction "d31_d31") (pintype "bidirectional"))
    )
    (net (code "86") (name "/TMS_TO_FMC") (class "Default")
      (node (ref "J4") (pin "d33") (pinfunction "d33_d33") (pintype "bidirectional"))
    )
    (net (code "87") (name "/TRST_TO_FMC") (class "Default")
      (node (ref "J4") (pin "d34") (pinfunction "d34_d34") (pintype "bidirectional"))
    )
    (net (code "88") (name "/USE_EXT_12V") (class "Default")
      (node (ref "R106") (pin "2") (pinfunction "2_2") (pintype "passive"))
      (node (ref "T9") (pin "1") (pinfunction "G_1") (pintype "passive"))
    )
    (net (code "89") (name "/VREF_A_M2C") (class "Default")
      (node (ref "J4") (pin "h1") (pinfunction "h1_h1") (pintype "bidirectional"))
    )
    (net (code "90") (name "GND") (class "Default")
      (node (ref "C158") (pin "1") (pinfunction "1_1") (pintype "passive"))
      (node (ref "C161") (pin "1") (pinfunction "1_1") (pintype "passive"))
      (node (ref "C172") (pin "1") (pinfunction "1_1") (pintype "passive"))
      (node (ref "C174") (pin "1") (pinfunction "1_1") (pintype "passive"))
      (node (ref "C19") (pin "1") (pinfunction "1_1") (pintype "passive"))
      (node (ref "C204") (pin "1") (pinfunction "1_1") (pintype "passive"))
      (node (ref "C205") (pin "1") (pinfunction "1_1") (pintype "passive"))
      (node (ref "C217") (pin "2") (pinfunction "2_2") (pintype "passive"))
      (node (ref "C221") (pin "1") (pinfunction "1_1") (pintype "passive"))
      (node (ref "C23") (pin "1") (pinfunction "1_1") (pintype "passive"))
      (node (ref "C26") (pin "1") (pinfunction "1_1") (pintype "passive"))
      (node (ref "C32") (pin "1") (pinfunction "1_1") (pintype "passive"))
      (node (ref "C33") (pin "1") (pinfunction "1_1") (pintype "passive"))
      (node (ref "C35") (pin "1") (pinfunction "1_1") (pintype "passive"))
      (node (ref "C37") (pin "1") (pinfunction "1_1") (pintype "passive"))
      (node (ref "C424") (pin "1") (pinfunction "1_1") (pintype "passive"))
      (node (ref "C431") (pin "1") (pinfunction "1_1") (pintype "passive"))
      (node (ref "C451") (pin "1") (pinfunction "1_1") (pintype "passive"))
      (node (ref "C454") (pin "1") (pinfunction "1_1") (pintype "passive"))
      (node (ref "C47") (pin "1") (pinfunction "1_1") (pintype "passive"))
      (node (ref "C48") (pin "1") (pinfunction "1_1") (pintype "passive"))
      (node (ref "C65") (pin "1") (pinfunction "1_1") (pintype "passive"))
      (node (ref "C69") (pin "1") (pinfunction "1_1") (pintype "passive"))
      (node (ref "C70") (pin "1") (pinfunction "1_1") (pintype "passive"))
      (node (ref "J4") (pin "c1") (pinfunction "c1_c1") (pintype "bidirectional"))
      (node (ref "J4") (pin "c12") (pinfunction "c12_c12") (pintype "bidirectional"))
      (node (ref "J4") (pin "c13") (pinfunction "c13_c13") (pintype "bidirectional"))
      (node (ref "J4") (pin "c16") (pinfunction "c16_c16") (pintype "bidirectional"))
      (node (ref "J4") (pin "c17") (pinfunction "c17_c17") (pintype "bidirectional"))
      (node (ref "J4") (pin "c20") (pinfunction "c20_c20") (pintype "bidirectional"))
      (node (ref "J4") (pin "c21") (pinfunction "c21_c21") (pintype "bidirectional"))
      (node (ref "J4") (pin "c24") (pinfunction "c24_c24") (pintype "bidirectional"))
      (node (ref "J4") (pin "c25") (pinfunction "c25_c25") (pintype "bidirectional"))
      (node (ref "J4") (pin "c28") (pinfunction "c28_c28") (pintype "bidirectional"))
      (node (ref "J4") (pin "c29") (pinfunction "c29_c29") (pintype "bidirectional"))
      (node (ref "J4") (pin "c32") (pinfunction "c32_c32") (pintype "bidirectional"))
      (node (ref "J4") (pin "c33") (pinfunction "c33_c33") (pintype "bidirectional"))
      (node (ref "J4") (pin "c34") (pinfunction "c34_c34") (pintype "bidirectional"))
      (node (ref "J4") (pin "c36") (pinfunction "c36_c36") (pintype "bidirectional"))
      (node (ref "J4") (pin "c38") (pinfunction "c38_c38") (pintype "bidirectional"))
      (node (ref "J4") (pin "c4") (pinfunction "c4_c4") (pintype "bidirectional"))
      (node (ref "J4") (pin "c40") (pinfunction "c40_c40") (pintype "bidirectional"))
      (node (ref "J4") (pin "c5") (pinfunction "c5_c5") (pintype "bidirectional"))
      (node (ref "J4") (pin "c8") (pinfunction "c8_c8") (pintype "bidirectional"))
      (node (ref "J4") (pin "c9") (pinfunction "c9_c9") (pintype "bidirectional"))
      (node (ref "J4") (pin "d10") (pinfunction "d10_d10") (pintype "bidirectional"))
      (node (ref "J4") (pin "d13") (pinfunction "d13_d13") (pintype "bidirectional"))
      (node (ref "J4") (pin "d16") (pinfunction "d16_d16") (pintype "bidirectional"))
      (node (ref "J4") (pin "d19") (pinfunction "d19_d19") (pintype "bidirectional"))
      (node (ref "J4") (pin "d2") (pinfunction "d2_d2") (pintype "bidirectional"))
      (node (ref "J4") (pin "d22") (pinfunction "d22_d22") (pintype "bidirectional"))
      (node (ref "J4") (pin "d25") (pinfunction "d25_d25") (pintype "bidirectional"))
      (node (ref "J4") (pin "d28") (pinfunction "d28_d28") (pintype "bidirectional"))
      (node (ref "J4") (pin "d3") (pinfunction "d3_d3") (pintype "bidirectional"))
      (node (ref "J4") (pin "d35") (pinfunction "d35_d35") (pintype "bidirectional"))
      (node (ref "J4") (pin "d37") (pinfunction "d37_d37") (pintype "bidirectional"))
      (node (ref "J4") (pin "d39") (pinfunction "d39_d39") (pintype "bidirectional"))
      (node (ref "J4") (pin "d6") (pinfunction "d6_d6") (pintype "bidirectional"))
      (node (ref "J4") (pin "d7") (pinfunction "d7_d7") (pintype "bidirectional"))
      (node (ref "J4") (pin "g1") (pinfunction "g1_g1") (pintype "bidirectional"))
      (node (ref "J4") (pin "g11") (pinfunction "g11_g11") (pintype "bidirectional"))
      (node (ref "J4") (pin "g14") (pinfunction "g14_g14") (pintype "bidirectional"))
      (node (ref "J4") (pin "g17") (pinfunction "g17_g17") (pintype "bidirectional"))
      (node (ref "J4") (pin "g20") (pinfunction "g20_g20") (pintype "bidirectional"))
      (node (ref "J4") (pin "g23") (pinfunction "g23_g23") (pintype "bidirectional"))
      (node (ref "J4") (pin "g26") (pinfunction "g26_g26") (pintype "bidirectional"))
      (node (ref "J4") (pin "g29") (pinfunction "g29_g29") (pintype "bidirectional"))
      (node (ref "J4") (pin "g32") (pinfunction "g32_g32") (pintype "bidirectional"))
      (node (ref "J4") (pin "g35") (pinfunction "g35_g35") (pintype "bidirectional"))
      (node (ref "J4") (pin "g38") (pinfunction "g38_g38") (pintype "bidirectional"))
      (node (ref "J4") (pin "g4") (pinfunction "g4_g4") (pintype "bidirectional"))
      (node (ref "J4") (pin "g40") (pinfunction "g40_g40") (pintype "bidirectional"))
      (node (ref "J4") (pin "g5") (pinfunction "g5_g5") (pintype "bidirectional"))
      (node (ref "J4") (pin "g8") (pinfunction "g8_g8") (pintype "bidirectional"))
      (node (ref "J4") (pin "h12") (pinfunction "h12_h12") (pintype "bidirectional"))
      (node (ref "J4") (pin "h15") (pinfunction "h15_h15") (pintype "bidirectional"))
      (node (ref "J4") (pin "h18") (pinfunction "h18_h18") (pintype "bidirectional"))
      (node (ref "J4") (pin "h21") (pinfunction "h21_h21") (pintype "bidirectional"))
      (node (ref "J4") (pin "h24") (pinfunction "h24_h24") (pintype "bidirectional"))
      (node (ref "J4") (pin "h27") (pinfunction "h27_h27") (pintype "bidirectional"))
      (node (ref "J4") (pin "h3") (pinfunction "h3_h3") (pintype "bidirectional"))
      (node (ref "J4") (pin "h30") (pinfunction "h30_h30") (pintype "bidirectional"))
      (node (ref "J4") (pin "h33") (pinfunction "h33_h33") (pintype "bidirectional"))
      (node (ref "J4") (pin "h36") (pinfunction "h36_h36") (pintype "bidirectional"))
      (node (ref "J4") (pin "h39") (pinfunction "h39_h39") (pintype "bidirectional"))
      (node (ref "J4") (pin "h6") (pinfunction "h6_h6") (pintype "bidirectional"))
      (node (ref "J4") (pin "h9") (pinfunction "h9_h9") (pintype "bidirectional"))
      (node (ref "M1") (pin "1") (pinfunction "1_1") (pintype "bidirectional"))
      (node (ref "M2") (pin "1") (pinfunction "1_1") (pintype "bidirectional"))
      (node (ref "M3") (pin "1") (pinfunction "1_1") (pintype "bidirectional"))
      (node (ref "M4") (pin "1") (pinfunction "1_1") (pintype "bidirectional"))
      (node (ref "M5") (pin "1") (pinfunction "1_1") (pintype "bidirectional"))
      (node (ref "M6") (pin "1") (pinfunction "1_1") (pintype "bidirectional"))
      (node (ref "M7") (pin "1") (pinfunction "1_1") (pintype "bidirectional"))
      (node (ref "M8") (pin "1") (pinfunction "1_1") (pintype "bidirectional"))
      (node (ref "T9") (pin "2") (pinfunction "S_2") (pintype "passive"))
    )
    (net (code "91") (name "Net-(T8-G)") (class "Default")
      (node (ref "R28") (pin "2") (pinfunction "2_2") (pintype "passive"))
      (node (ref "T8") (pin "1") (pinfunction "G_1") (pintype "passive"))
      (node (ref "T9") (pin "3") (pinfunction "D_3") (pintype "passive"))
    )
    (net (code "92") (name "P2V5") (class "Default")
      (node (ref "C158") (pin "2") (pinfunction "2_2") (pintype "passive"))
      (node (ref "C172") (pin "2") (pinfunction "2_2") (pintype "passive"))
      (node (ref "C174") (pin "2") (pinfunction "2_2") (pintype "passive"))
      (node (ref "C19") (pin "2") (pinfunction "2_2") (pintype "passive"))
      (node (ref "C204") (pin "2") (pinfunction "2_2") (pintype "passive"))
      (node (ref "C205") (pin "2") (pinfunction "2_2") (pintype "passive"))
      (node (ref "C221") (pin "2") (pinfunction "2_2") (pintype "passive"))
      (node (ref "C32") (pin "2") (pinfunction "2_2") (pintype "passive"))
      (node (ref "C431") (pin "2") (pinfunction "2_2") (pintype "passive"))
      (node (ref "C48") (pin "2") (pinfunction "2_2") (pintype "passive"))
      (node (ref "C65") (pin "2") (pinfunction "2_2") (pintype "passive"))
      (node (ref "C69") (pin "2") (pinfunction "2_2") (pintype "passive"))
      (node (ref "C70") (pin "2") (pinfunction "2_2") (pintype "passive"))
      (node (ref "J4") (pin "g39") (pinfunction "g39_g39") (pintype "bidirectional"))
      (node (ref "J4") (pin "h40") (pinfunction "h40_h40") (pintype "bidirectional"))
      (node (ref "R425") (pin "2") (pinfunction "2_2") (pintype "passive"))
      (node (ref "R426") (pin "2") (pinfunction "2_2") (pintype "passive"))
    )
    (net (code "93") (name "P3V3") (class "Default")
      (node (ref "R106") (pin "1") (pinfunction "1_1") (pintype "passive"))
      (node (ref "R28") (pin "1") (pinfunction "1_1") (pintype "passive"))
      (node (ref "T8") (pin "2") (pinfunction "S_2") (pintype "passive"))
    )
    (net (code "94") (name "P3V3_FMC") (class "Default")
      (node (ref "C161") (pin "2") (pinfunction "2_2") (pintype "passive"))
      (node (ref "C23") (pin "2") (pinfunction "2_2") (pintype "passive"))
      (node (ref "C26") (pin "2") (pinfunction "2_2") (pintype "passive"))
      (node (ref "C37") (pin "2") (pinfunction "2_2") (pintype "passive"))
      (node (ref "C451") (pin "2") (pinfunction "2_2") (pintype "passive"))
      (node (ref "C454") (pin "2") (pinfunction "2_2") (pintype "passive"))
      (node (ref "C47") (pin "2") (pinfunction "2_2") (pintype "passive"))
      (node (ref "F3") (pin "2") (pinfunction "2_2") (pintype "passive"))
      (node (ref "J4") (pin "c39") (pinfunction "c39_c39") (pintype "bidirectional"))
      (node (ref "J4") (pin "d32") (pinfunction "d32_d32") (pintype "bidirectional"))
      (node (ref "J4") (pin "d36") (pinfunction "d36_d36") (pintype "bidirectional"))
      (node (ref "J4") (pin "d38") (pinfunction "d38_d38") (pintype "bidirectional"))
      (node (ref "J4") (pin "d40") (pinfunction "d40_d40") (pintype "bidirectional"))
    )
    (net (code "95") (name "P3V3_PCIE") (class "Default")
      (node (ref "F3") (pin "1") (pinfunction "1_1") (pintype "passive"))
      (node (ref "T8") (pin "3") (pinfunction "D_3") (pintype "passive"))
    )
    (net (code "96") (name "P12V") (class "Default")
      (node (ref "C217") (pin "1") (pinfunction "1_1") (pintype "passive"))
      (node (ref "C33") (pin "2") (pinfunction "2_2") (pintype "passive"))
      (node (ref "C35") (pin "2") (pinfunction "2_2") (pintype "passive"))
      (node (ref "C424") (pin "2") (pinfunction "2_2") (pintype "passive"))
      (node (ref "J4") (pin "c35") (pinfunction "c35_c35") (pintype "bidirectional"))
      (node (ref "J4") (pin "c37") (pinfunction "c37_c37") (pintype "bidirectional"))
    )
  )
)
